# schematic.net
KiCad netlist of a schematic drawn in EAGLE
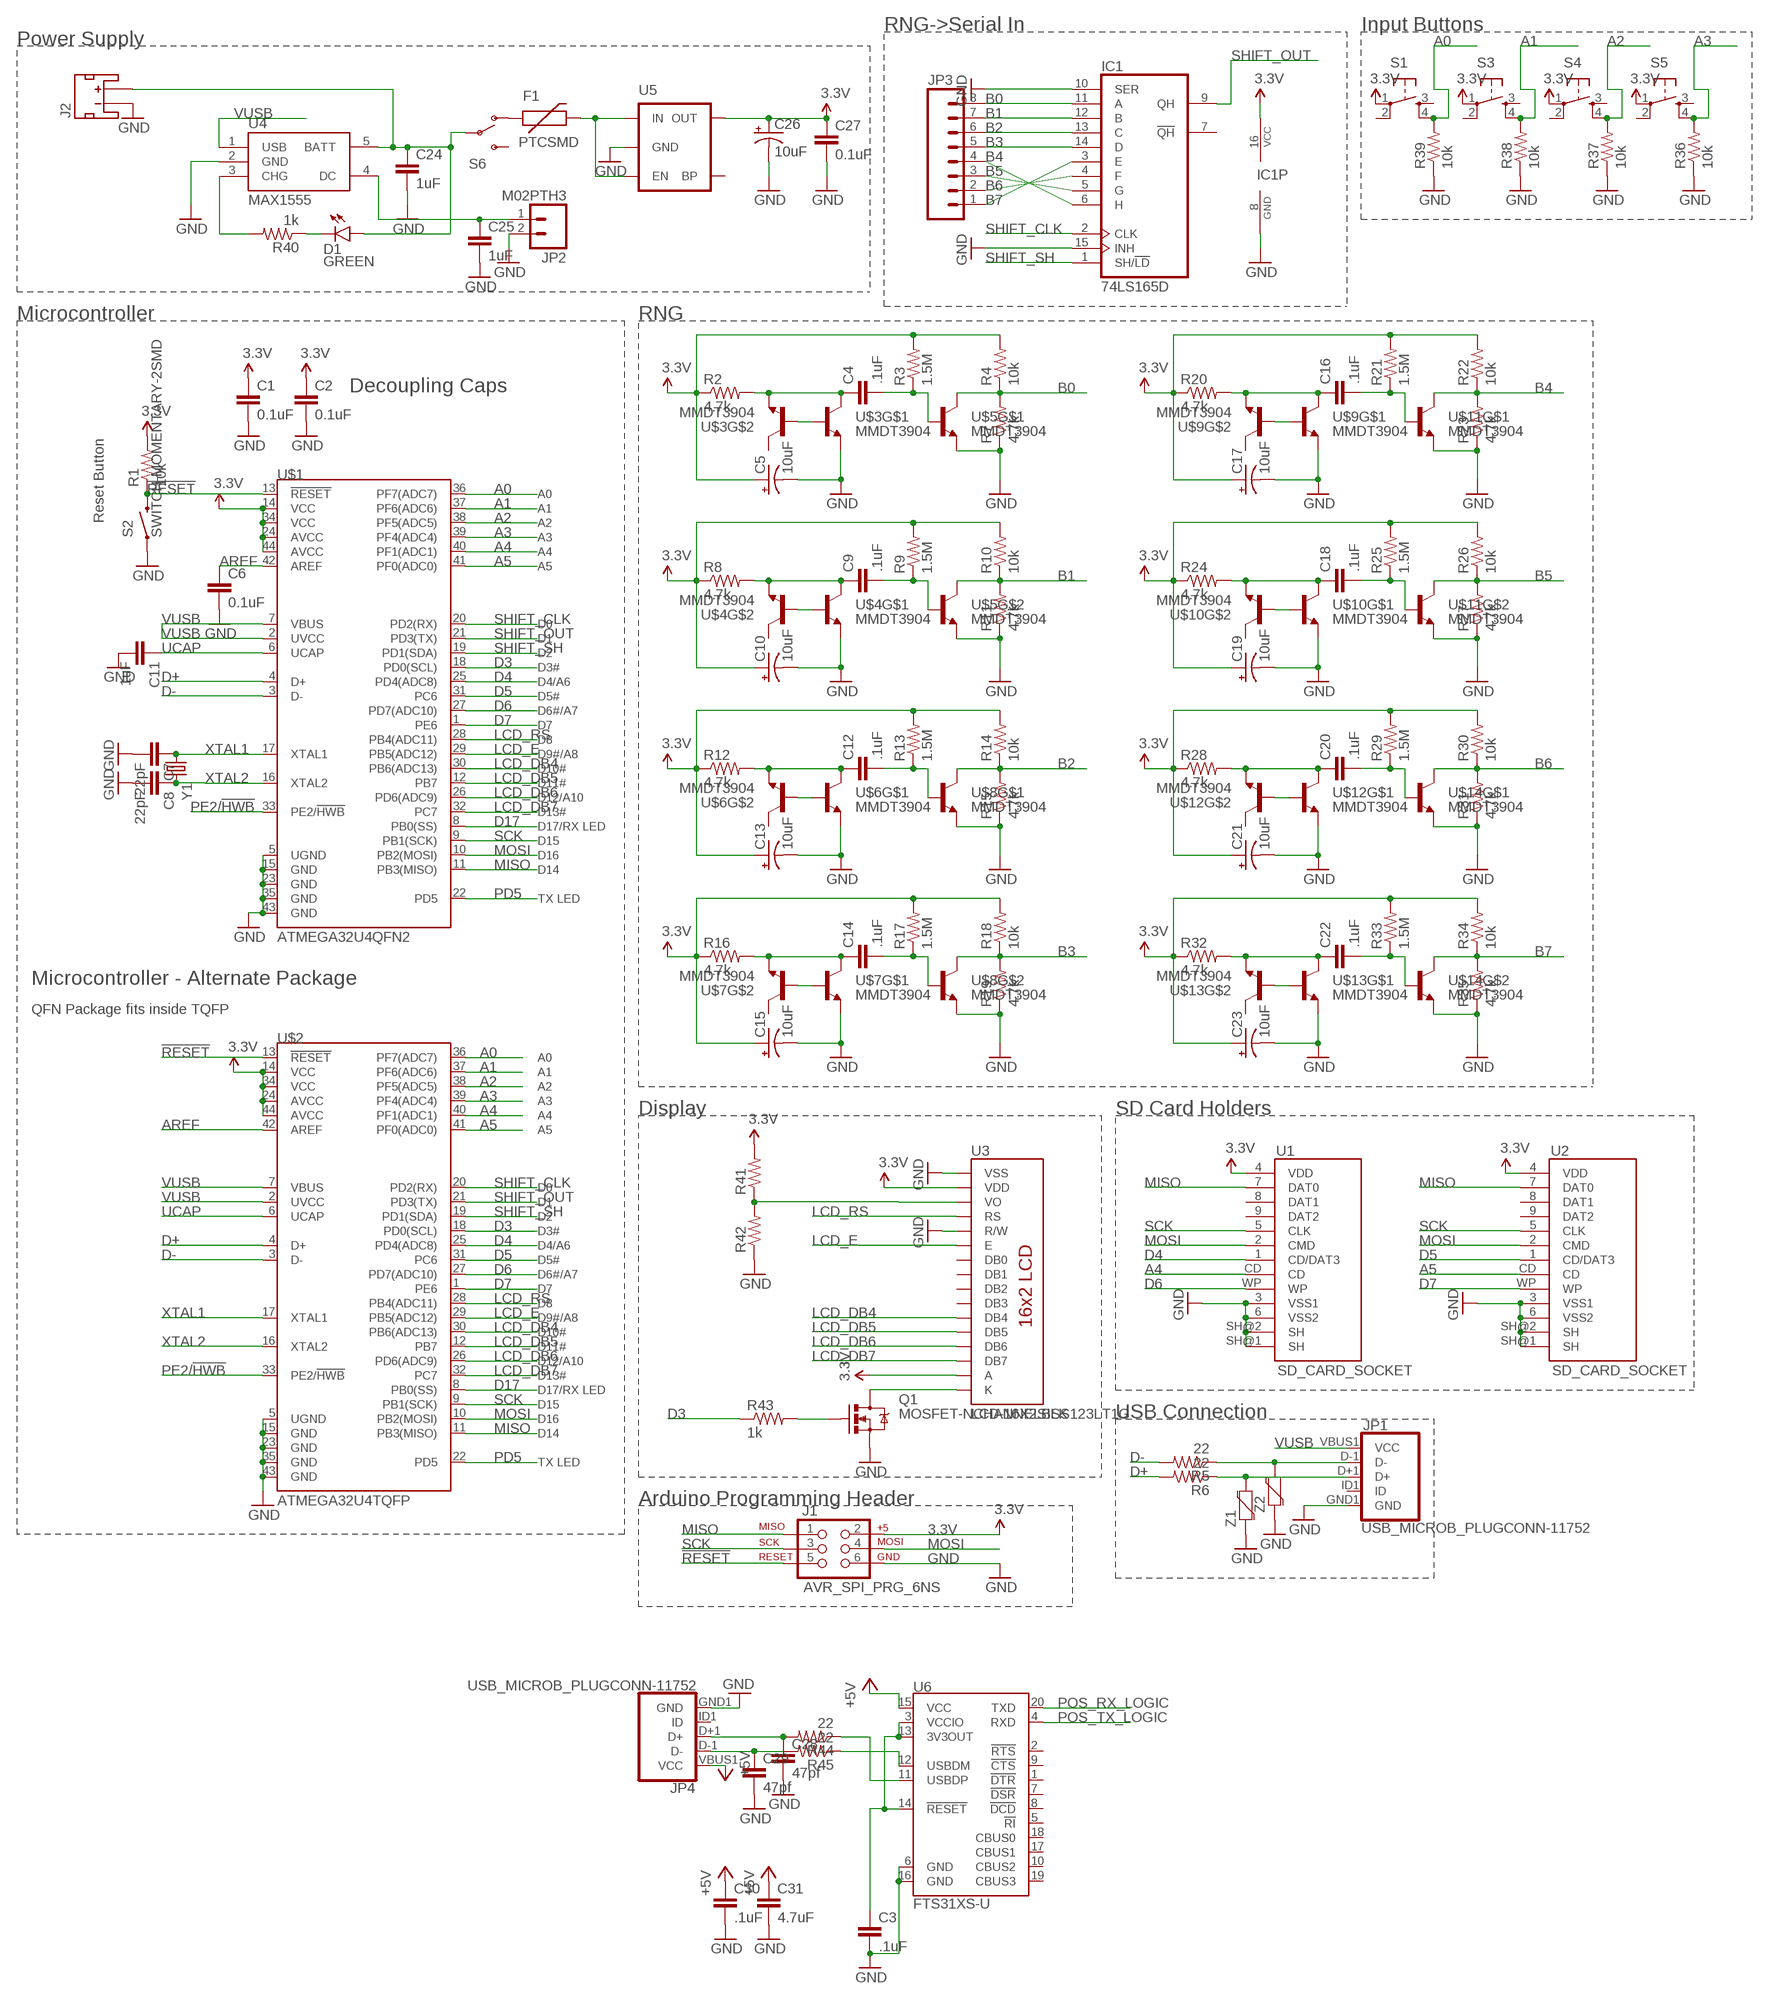
[diagram p0: schematic, sheet 1]

(export (version "E")
  (design (tool "Eeschema 10.0.6"))
  (components
    (comp (ref "C1")
      (value "0.1uF")
      (footprint "eagle-import:0603-CAP")
      (libsource (lib "eagle-import") (part "CAP0603-CAP"))
    )
    (comp (ref "C2")
      (value "0.1uF")
      (footprint "eagle-import:0603-CAP")
      (libsource (lib "eagle-import") (part "CAP0603-CAP"))
    )
    (comp (ref "C3")
      (value ".1uF")
      (footprint "eagle-import:0603-CAP")
      (libsource (lib "eagle-import") (part "CAP0603-CAP"))
    )
    (comp (ref "C4")
      (value ".1uF")
      (footprint "eagle-import:0603-CAP")
      (libsource (lib "eagle-import") (part "CAP0603-CAP"))
    )
    (comp (ref "C5")
      (value "10uF")
      (footprint "eagle-import:EIA3216")
      (libsource (lib "eagle-import") (part "CAP_POL1206"))
    )
    (comp (ref "C6")
      (value "0.1uF")
      (footprint "eagle-import:0603-CAP")
      (libsource (lib "eagle-import") (part "CAP0603-CAP"))
    )
    (comp (ref "C7")
      (value "22pF")
      (footprint "eagle-import:0603-CAP")
      (libsource (lib "eagle-import") (part "CAP0603-CAP"))
    )
    (comp (ref "C8")
      (value "22pF")
      (footprint "eagle-import:0603-CAP")
      (libsource (lib "eagle-import") (part "CAP0603-CAP"))
    )
    (comp (ref "C9")
      (value ".1uF")
      (footprint "eagle-import:0603-CAP")
      (libsource (lib "eagle-import") (part "CAP0603-CAP"))
    )
    (comp (ref "C10")
      (value "10uF")
      (footprint "eagle-import:EIA3216")
      (libsource (lib "eagle-import") (part "CAP_POL1206"))
    )
    (comp (ref "C11")
      (value "1uF")
      (footprint "eagle-import:0603-CAP")
      (libsource (lib "eagle-import") (part "CAP0603-CAP"))
    )
    (comp (ref "C12")
      (value ".1uF")
      (footprint "eagle-import:0603-CAP")
      (libsource (lib "eagle-import") (part "CAP0603-CAP"))
    )
    (comp (ref "C13")
      (value "10uF")
      (footprint "eagle-import:EIA3216")
      (libsource (lib "eagle-import") (part "CAP_POL1206"))
    )
    (comp (ref "C14")
      (value ".1uF")
      (footprint "eagle-import:0603-CAP")
      (libsource (lib "eagle-import") (part "CAP0603-CAP"))
    )
    (comp (ref "C15")
      (value "10uF")
      (footprint "eagle-import:EIA3216")
      (libsource (lib "eagle-import") (part "CAP_POL1206"))
    )
    (comp (ref "C16")
      (value ".1uF")
      (footprint "eagle-import:0603-CAP")
      (libsource (lib "eagle-import") (part "CAP0603-CAP"))
    )
    (comp (ref "C17")
      (value "10uF")
      (footprint "eagle-import:EIA3216")
      (libsource (lib "eagle-import") (part "CAP_POL1206"))
    )
    (comp (ref "C18")
      (value ".1uF")
      (footprint "eagle-import:0603-CAP")
      (libsource (lib "eagle-import") (part "CAP0603-CAP"))
    )
    (comp (ref "C19")
      (value "10uF")
      (footprint "eagle-import:EIA3216")
      (libsource (lib "eagle-import") (part "CAP_POL1206"))
    )
    (comp (ref "C20")
      (value ".1uF")
      (footprint "eagle-import:0603-CAP")
      (libsource (lib "eagle-import") (part "CAP0603-CAP"))
    )
    (comp (ref "C21")
      (value "10uF")
      (footprint "eagle-import:EIA3216")
      (libsource (lib "eagle-import") (part "CAP_POL1206"))
    )
    (comp (ref "C22")
      (value ".1uF")
      (footprint "eagle-import:0603-CAP")
      (libsource (lib "eagle-import") (part "CAP0603-CAP"))
    )
    (comp (ref "C23")
      (value "10uF")
      (footprint "eagle-import:EIA3216")
      (libsource (lib "eagle-import") (part "CAP_POL1206"))
    )
    (comp (ref "C24")
      (value "1uF")
      (footprint "eagle-import:0603-CAP")
      (libsource (lib "eagle-import") (part "CAP0603-CAP"))
    )
    (comp (ref "C25")
      (value "1uF")
      (footprint "eagle-import:0603-CAP")
      (libsource (lib "eagle-import") (part "CAP0603-CAP"))
    )
    (comp (ref "C26")
      (value "10uF")
      (footprint "eagle-import:EIA3216")
      (libsource (lib "eagle-import") (part "CAP_POL1206"))
    )
    (comp (ref "C27")
      (value "0.1uF")
      (footprint "eagle-import:0603-CAP")
      (libsource (lib "eagle-import") (part "CAP0603-CAP"))
    )
    (comp (ref "C28")
      (value "47pf")
      (footprint "eagle-import:0603-CAP")
      (libsource (lib "eagle-import") (part "CAP0603-CAP"))
    )
    (comp (ref "C29")
      (value "47pf")
      (footprint "eagle-import:0603-CAP")
      (libsource (lib "eagle-import") (part "CAP0603-CAP"))
    )
    (comp (ref "C30")
      (value ".1uF")
      (footprint "eagle-import:0603-CAP")
      (libsource (lib "eagle-import") (part "CAP0603-CAP"))
    )
    (comp (ref "C31")
      (value "4.7uF")
      (footprint "eagle-import:0603-CAP")
      (libsource (lib "eagle-import") (part "CAP0603-CAP"))
    )
    (comp (ref "D1")
      (value "GREEN")
      (footprint "eagle-import:LED-0603")
      (libsource (lib "eagle-import") (part "LED-GREEN0603"))
    )
    (comp (ref "F1")
      (value "PTCSMD")
      (footprint "eagle-import:PTC-1206")
      (libsource (lib "eagle-import") (part "PTCSMD"))
    )
    (comp (ref "IC1")
      (value "74LS165D")
      (footprint "eagle-import:SO16")
      (libsource (lib "eagle-import") (part "74165DLS"))
    )
    (comp (ref "J1")
      (value "AVR_SPI_PRG_6NS")
      (footprint "eagle-import:2X3-NS")
      (libsource (lib "eagle-import") (part "AVR_SPI_PRG_6NS"))
    )
    (comp (ref "J2")
      (value "JST_2MM_MALE")
      (footprint "eagle-import:JST-2-SMD")
      (libsource (lib "eagle-import") (part "JST_2MM_MALE"))
    )
    (comp (ref "JP1")
      (value "USB_MICROB_PLUGCONN-11752")
      (footprint "eagle-import:USB-B-MICRO-SMD_V03")
      (libsource (lib "eagle-import") (part "USB_MICROB_PLUGCONN-11752"))
    )
    (comp (ref "JP2")
      (value "M02PTH3")
      (footprint "eagle-import:1X02_LONGPADS")
      (libsource (lib "eagle-import") (part "M02PTH3"))
    )
    (comp (ref "JP3")
      (value "M081X08")
      (footprint "eagle-import:1X08")
      (libsource (lib "eagle-import") (part "M081X08"))
    )
    (comp (ref "JP4")
      (value "USB_MICROB_PLUGCONN-11752")
      (footprint "eagle-import:USB-B-MICRO-SMD_V03")
      (libsource (lib "eagle-import") (part "USB_MICROB_PLUGCONN-11752"))
    )
    (comp (ref "Q1")
      (value "MOSFET-NCHANNELBSS123LT1G")
      (footprint "eagle-import:SOT23")
      (libsource (lib "eagle-import") (part "MOSFET-NCHANNELBSS123LT1G"))
    )
    (comp (ref "R1")
      (value "10k")
      (footprint "eagle-import:0603-RES")
      (libsource (lib "eagle-import") (part "RESISTOR0603-RES"))
    )
    (comp (ref "R2")
      (value "4.7k")
      (footprint "eagle-import:0603-RES")
      (libsource (lib "eagle-import") (part "RESISTOR0603-RES"))
    )
    (comp (ref "R3")
      (value "1.5M")
      (footprint "eagle-import:0603-RES")
      (libsource (lib "eagle-import") (part "RESISTOR0603-RES"))
    )
    (comp (ref "R4")
      (value "10k")
      (footprint "eagle-import:0603-RES")
      (libsource (lib "eagle-import") (part "RESISTOR0603-RES"))
    )
    (comp (ref "R5")
      (value "22")
      (footprint "eagle-import:0603-RES")
      (libsource (lib "eagle-import") (part "RESISTOR0603-RES"))
    )
    (comp (ref "R6")
      (value "22")
      (footprint "eagle-import:0603-RES")
      (libsource (lib "eagle-import") (part "RESISTOR0603-RES"))
    )
    (comp (ref "R7")
      (value "4.7k")
      (footprint "eagle-import:0603-RES")
      (libsource (lib "eagle-import") (part "RESISTOR0603-RES"))
    )
    (comp (ref "R8")
      (value "4.7k")
      (footprint "eagle-import:0603-RES")
      (libsource (lib "eagle-import") (part "RESISTOR0603-RES"))
    )
    (comp (ref "R9")
      (value "1.5M")
      (footprint "eagle-import:0603-RES")
      (libsource (lib "eagle-import") (part "RESISTOR0603-RES"))
    )
    (comp (ref "R10")
      (value "10k")
      (footprint "eagle-import:0603-RES")
      (libsource (lib "eagle-import") (part "RESISTOR0603-RES"))
    )
    (comp (ref "R11")
      (value "4.7k")
      (footprint "eagle-import:0603-RES")
      (libsource (lib "eagle-import") (part "RESISTOR0603-RES"))
    )
    (comp (ref "R12")
      (value "4.7k")
      (footprint "eagle-import:0603-RES")
      (libsource (lib "eagle-import") (part "RESISTOR0603-RES"))
    )
    (comp (ref "R13")
      (value "1.5M")
      (footprint "eagle-import:0603-RES")
      (libsource (lib "eagle-import") (part "RESISTOR0603-RES"))
    )
    (comp (ref "R14")
      (value "10k")
      (footprint "eagle-import:0603-RES")
      (libsource (lib "eagle-import") (part "RESISTOR0603-RES"))
    )
    (comp (ref "R15")
      (value "4.7k")
      (footprint "eagle-import:0603-RES")
      (libsource (lib "eagle-import") (part "RESISTOR0603-RES"))
    )
    (comp (ref "R16")
      (value "4.7k")
      (footprint "eagle-import:0603-RES")
      (libsource (lib "eagle-import") (part "RESISTOR0603-RES"))
    )
    (comp (ref "R17")
      (value "1.5M")
      (footprint "eagle-import:0603-RES")
      (libsource (lib "eagle-import") (part "RESISTOR0603-RES"))
    )
    (comp (ref "R18")
      (value "10k")
      (footprint "eagle-import:0603-RES")
      (libsource (lib "eagle-import") (part "RESISTOR0603-RES"))
    )
    (comp (ref "R19")
      (value "4.7k")
      (footprint "eagle-import:0603-RES")
      (libsource (lib "eagle-import") (part "RESISTOR0603-RES"))
    )
    (comp (ref "R20")
      (value "4.7k")
      (footprint "eagle-import:0603-RES")
      (libsource (lib "eagle-import") (part "RESISTOR0603-RES"))
    )
    (comp (ref "R21")
      (value "1.5M")
      (footprint "eagle-import:0603-RES")
      (libsource (lib "eagle-import") (part "RESISTOR0603-RES"))
    )
    (comp (ref "R22")
      (value "10k")
      (footprint "eagle-import:0603-RES")
      (libsource (lib "eagle-import") (part "RESISTOR0603-RES"))
    )
    (comp (ref "R23")
      (value "4.7k")
      (footprint "eagle-import:0603-RES")
      (libsource (lib "eagle-import") (part "RESISTOR0603-RES"))
    )
    (comp (ref "R24")
      (value "4.7k")
      (footprint "eagle-import:0603-RES")
      (libsource (lib "eagle-import") (part "RESISTOR0603-RES"))
    )
    (comp (ref "R25")
      (value "1.5M")
      (footprint "eagle-import:0603-RES")
      (libsource (lib "eagle-import") (part "RESISTOR0603-RES"))
    )
    (comp (ref "R26")
      (value "10k")
      (footprint "eagle-import:0603-RES")
      (libsource (lib "eagle-import") (part "RESISTOR0603-RES"))
    )
    (comp (ref "R27")
      (value "4.7k")
      (footprint "eagle-import:0603-RES")
      (libsource (lib "eagle-import") (part "RESISTOR0603-RES"))
    )
    (comp (ref "R28")
      (value "4.7k")
      (footprint "eagle-import:0603-RES")
      (libsource (lib "eagle-import") (part "RESISTOR0603-RES"))
    )
    (comp (ref "R29")
      (value "1.5M")
      (footprint "eagle-import:0603-RES")
      (libsource (lib "eagle-import") (part "RESISTOR0603-RES"))
    )
    (comp (ref "R30")
      (value "10k")
      (footprint "eagle-import:0603-RES")
      (libsource (lib "eagle-import") (part "RESISTOR0603-RES"))
    )
    (comp (ref "R31")
      (value "4.7k")
      (footprint "eagle-import:0603-RES")
      (libsource (lib "eagle-import") (part "RESISTOR0603-RES"))
    )
    (comp (ref "R32")
      (value "4.7k")
      (footprint "eagle-import:0603-RES")
      (libsource (lib "eagle-import") (part "RESISTOR0603-RES"))
    )
    (comp (ref "R33")
      (value "1.5M")
      (footprint "eagle-import:0603-RES")
      (libsource (lib "eagle-import") (part "RESISTOR0603-RES"))
    )
    (comp (ref "R34")
      (value "10k")
      (footprint "eagle-import:0603-RES")
      (libsource (lib "eagle-import") (part "RESISTOR0603-RES"))
    )
    (comp (ref "R35")
      (value "4.7k")
      (footprint "eagle-import:0603-RES")
      (libsource (lib "eagle-import") (part "RESISTOR0603-RES"))
    )
    (comp (ref "R36")
      (value "10k")
      (footprint "eagle-import:0603-RES")
      (libsource (lib "eagle-import") (part "RESISTOR0603-RES"))
    )
    (comp (ref "R37")
      (value "10k")
      (footprint "eagle-import:0603-RES")
      (libsource (lib "eagle-import") (part "RESISTOR0603-RES"))
    )
    (comp (ref "R38")
      (value "10k")
      (footprint "eagle-import:0603-RES")
      (libsource (lib "eagle-import") (part "RESISTOR0603-RES"))
    )
    (comp (ref "R39")
      (value "10k")
      (footprint "eagle-import:0603-RES")
      (libsource (lib "eagle-import") (part "RESISTOR0603-RES"))
    )
    (comp (ref "R40")
      (value "1k")
      (footprint "eagle-import:0603-RES")
      (libsource (lib "eagle-import") (part "RESISTOR0603-RES"))
    )
    (comp (ref "R41")
      (value "RESISTOR0603-RES")
      (footprint "eagle-import:0603-RES")
      (libsource (lib "eagle-import") (part "RESISTOR0603-RES"))
    )
    (comp (ref "R42")
      (value "RESISTOR0603-RES")
      (footprint "eagle-import:0603-RES")
      (libsource (lib "eagle-import") (part "RESISTOR0603-RES"))
    )
    (comp (ref "R43")
      (value "1k")
      (footprint "eagle-import:0603-RES")
      (libsource (lib "eagle-import") (part "RESISTOR0603-RES"))
    )
    (comp (ref "R44")
      (value "22")
      (footprint "eagle-import:0603-RES")
      (libsource (lib "eagle-import") (part "RESISTOR0603-RES"))
    )
    (comp (ref "R45")
      (value "22")
      (footprint "eagle-import:0603-RES")
      (libsource (lib "eagle-import") (part "RESISTOR0603-RES"))
    )
    (comp (ref "S1")
      (value "TAC_SWITCHPTH")
      (footprint "eagle-import:TACTILE-PTH")
      (libsource (lib "eagle-import") (part "TAC_SWITCHPTH"))
    )
    (comp (ref "S2")
      (value "SWITCH-MOMENTARY-2SMD")
      (footprint "eagle-import:TACTILE-SWITCH-SMD")
      (libsource (lib "eagle-import") (part "SWITCH-MOMENTARY-2SMD"))
    )
    (comp (ref "S3")
      (value "TAC_SWITCHPTH")
      (footprint "eagle-import:TACTILE-PTH")
      (libsource (lib "eagle-import") (part "TAC_SWITCHPTH"))
    )
    (comp (ref "S4")
      (value "TAC_SWITCHPTH")
      (footprint "eagle-import:TACTILE-PTH")
      (libsource (lib "eagle-import") (part "TAC_SWITCHPTH"))
    )
    (comp (ref "S5")
      (value "TAC_SWITCHPTH")
      (footprint "eagle-import:TACTILE-PTH")
      (libsource (lib "eagle-import") (part "TAC_SWITCHPTH"))
    )
    (comp (ref "S6")
      (value "SWITCH-SPDTPTH")
      (footprint "eagle-import:SWITCH-SPDT")
      (libsource (lib "eagle-import") (part "SWITCH-SPDTPTH"))
    )
    (comp (ref "U$1")
      (value "ATMEGA32U4QFN2")
      (footprint "eagle-import:SPARKFUN-DIGITALIC_QFN-44-NOPAD")
      (libsource (lib "eagle-import") (part "ATMEGA32U4QFN2"))
    )
    (comp (ref "U$2")
      (value "ATMEGA32U4TQFP")
      (footprint "eagle-import:SPARKFUN-DIGITALIC_TQFP44")
      (libsource (lib "eagle-import") (part "ATMEGA32U4TQFP"))
    )
    (comp (ref "U$3")
      (value "MMDT3904")
      (footprint "eagle-import:SOT363")
      (libsource (lib "eagle-import") (part "TRANSISTOR_NPN2UPMMDT3904"))
    )
    (comp (ref "U$4")
      (value "MMDT3904")
      (footprint "eagle-import:SOT363")
      (libsource (lib "eagle-import") (part "TRANSISTOR_NPN2UPMMDT3904"))
    )
    (comp (ref "U$5")
      (value "MMDT3904")
      (footprint "eagle-import:SOT363")
      (libsource (lib "eagle-import") (part "TRANSISTOR_NPN2UPMMDT3904"))
    )
    (comp (ref "U$6")
      (value "MMDT3904")
      (footprint "eagle-import:SOT363")
      (libsource (lib "eagle-import") (part "TRANSISTOR_NPN2UPMMDT3904"))
    )
    (comp (ref "U$7")
      (value "MMDT3904")
      (footprint "eagle-import:SOT363")
      (libsource (lib "eagle-import") (part "TRANSISTOR_NPN2UPMMDT3904"))
    )
    (comp (ref "U$8")
      (value "MMDT3904")
      (footprint "eagle-import:SOT363")
      (libsource (lib "eagle-import") (part "TRANSISTOR_NPN2UPMMDT3904"))
    )
    (comp (ref "U$9")
      (value "MMDT3904")
      (footprint "eagle-import:SOT363")
      (libsource (lib "eagle-import") (part "TRANSISTOR_NPN2UPMMDT3904"))
    )
    (comp (ref "U$10")
      (value "MMDT3904")
      (footprint "eagle-import:SOT363")
      (libsource (lib "eagle-import") (part "TRANSISTOR_NPN2UPMMDT3904"))
    )
    (comp (ref "U$11")
      (value "MMDT3904")
      (footprint "eagle-import:SOT363")
      (libsource (lib "eagle-import") (part "TRANSISTOR_NPN2UPMMDT3904"))
    )
    (comp (ref "U$12")
      (value "MMDT3904")
      (footprint "eagle-import:SOT363")
      (libsource (lib "eagle-import") (part "TRANSISTOR_NPN2UPMMDT3904"))
    )
    (comp (ref "U$13")
      (value "MMDT3904")
      (footprint "eagle-import:SOT363")
      (libsource (lib "eagle-import") (part "TRANSISTOR_NPN2UPMMDT3904"))
    )
    (comp (ref "U$14")
      (value "MMDT3904")
      (footprint "eagle-import:SOT363")
      (libsource (lib "eagle-import") (part "TRANSISTOR_NPN2UPMMDT3904"))
    )
    (comp (ref "U1")
      (value "SD_CARD_SOCKET")
      (footprint "eagle-import:SD_1_1")
      (libsource (lib "eagle-import") (part "SD_CARD_SOCKET"))
    )
    (comp (ref "U2")
      (value "SD_CARD_SOCKET")
      (footprint "eagle-import:SD_1_1")
      (libsource (lib "eagle-import") (part "SD_CARD_SOCKET"))
    )
    (comp (ref "U3")
      (value "LCD-16X2SILK")
      (footprint "eagle-import:LCD-16X2")
      (libsource (lib "eagle-import") (part "LCD-16X2SILK"))
    )
    (comp (ref "U4")
      (value "MAX1555")
      (footprint "eagle-import:SOT23-5")
      (libsource (lib "eagle-import") (part "MAX1555"))
    )
    (comp (ref "U5")
      (value "MIC52053.3V")
      (footprint "eagle-import:SOT23-5")
      (libsource (lib "eagle-import") (part "MIC52053.3V"))
    )
    (comp (ref "U6")
      (value "FTS31XS-U")
      (footprint "eagle-import:SSOP20_L")
      (libsource (lib "eagle-import") (part "FT231XS"))
    )
    (comp (ref "Y1")
      (value "CRYSTALSMD")
      (footprint "eagle-import:HC49UP")
      (libsource (lib "eagle-import") (part "CRYSTALSMD"))
    )
    (comp (ref "Z1")
      (value "VARISTOR-0603")
      (footprint "eagle-import:0603-RES")
      (libsource (lib "eagle-import") (part "VARISTOR-0603"))
    )
    (comp (ref "Z2")
      (value "VARISTOR-0603")
      (footprint "eagle-import:0603-RES")
      (libsource (lib "eagle-import") (part "VARISTOR-0603"))
    )
  )
  (nets
    (net (code "1") (name "+5V") (class "Default")
      (node (ref "C30") (pin "1") (pinfunction "1_1") (pintype "passive"))
      (node (ref "C31") (pin "1") (pinfunction "1_1") (pintype "passive"))
      (node (ref "JP4") (pin "VBUS1") (pinfunction "VCC_VBUS1") (pintype "bidirectional"))
      (node (ref "U6") (pin "15") (pinfunction "VCC_15") (pintype "bidirectional"))
    )
    (net (code "2") (name "/A0") (class "Default")
      (node (ref "R39") (pin "2") (pinfunction "2_2") (pintype "passive"))
      (node (ref "S1") (pin "4") (pinfunction "4_4") (pintype "passive"))
      (node (ref "U$1") (pin "36") (pinfunction "PF7(ADC7)_36") (pintype "bidirectional"))
      (node (ref "U$2") (pin "36") (pinfunction "PF7(ADC7)_36") (pintype "bidirectional"))
    )
    (net (code "3") (name "/A1") (class "Default")
      (node (ref "R38") (pin "2") (pinfunction "2_2") (pintype "passive"))
      (node (ref "S3") (pin "4") (pinfunction "4_4") (pintype "passive"))
      (node (ref "U$1") (pin "37") (pinfunction "PF6(ADC6)_37") (pintype "bidirectional"))
      (node (ref "U$2") (pin "37") (pinfunction "PF6(ADC6)_37") (pintype "bidirectional"))
    )
    (net (code "4") (name "/A2") (class "Default")
      (node (ref "R37") (pin "2") (pinfunction "2_2") (pintype "passive"))
      (node (ref "S4") (pin "4") (pinfunction "4_4") (pintype "passive"))
      (node (ref "U$1") (pin "38") (pinfunction "PF5(ADC5)_38") (pintype "bidirectional"))
      (node (ref "U$2") (pin "38") (pinfunction "PF5(ADC5)_38") (pintype "bidirectional"))
    )
    (net (code "5") (name "/A3") (class "Default")
      (node (ref "R36") (pin "2") (pinfunction "2_2") (pintype "passive"))
      (node (ref "S5") (pin "4") (pinfunction "4_4") (pintype "passive"))
      (node (ref "U$1") (pin "39") (pinfunction "PF4(ADC4)_39") (pintype "bidirectional"))
      (node (ref "U$2") (pin "39") (pinfunction "PF4(ADC4)_39") (pintype "bidirectional"))
    )
    (net (code "6") (name "/A4") (class "Default")
      (node (ref "U$1") (pin "40") (pinfunction "PF1(ADC1)_40") (pintype "bidirectional"))
      (node (ref "U$2") (pin "40") (pinfunction "PF1(ADC1)_40") (pintype "bidirectional"))
      (node (ref "U1") (pin "CD") (pinfunction "CD_CD") (pintype "bidirectional"))
    )
    (net (code "7") (name "/A5") (class "Default")
      (node (ref "U$1") (pin "41") (pinfunction "PF0(ADC0)_41") (pintype "bidirectional"))
      (node (ref "U$2") (pin "41") (pinfunction "PF0(ADC0)_41") (pintype "bidirectional"))
      (node (ref "U2") (pin "CD") (pinfunction "CD_CD") (pintype "bidirectional"))
    )
    (net (code "8") (name "/AREF") (class "Default")
      (node (ref "C6") (pin "1") (pinfunction "1_1") (pintype "passive"))
      (node (ref "U$1") (pin "42") (pinfunction "AREF_42") (pintype "bidirectional"))
      (node (ref "U$2") (pin "42") (pinfunction "AREF_42") (pintype "bidirectional"))
    )
    (net (code "9") (name "/B0") (class "Default")
      (node (ref "IC1") (pin "11") (pinfunction "A_11") (pintype "input"))
      (node (ref "JP3") (pin "8") (pinfunction "8_8") (pintype "passive"))
      (node (ref "R4") (pin "1") (pinfunction "1_1") (pintype "passive"))
      (node (ref "R7") (pin "2") (pinfunction "2_2") (pintype "passive"))
      (node (ref "U$5") (pin "6") (pinfunction "C_6") (pintype "passive"))
    )
    (net (code "10") (name "/B1") (class "Default")
      (node (ref "IC1") (pin "12") (pinfunction "B_12") (pintype "input"))
      (node (ref "JP3") (pin "7") (pinfunction "7_7") (pintype "passive"))
      (node (ref "R10") (pin "1") (pinfunction "1_1") (pintype "passive"))
      (node (ref "R11") (pin "2") (pinfunction "2_2") (pintype "passive"))
      (node (ref "U$5") (pin "3") (pinfunction "C_3") (pintype "passive"))
    )
    (net (code "11") (name "/B2") (class "Default")
      (node (ref "IC1") (pin "13") (pinfunction "C_13") (pintype "input"))
      (node (ref "JP3") (pin "6") (pinfunction "6_6") (pintype "passive"))
      (node (ref "R14") (pin "1") (pinfunction "1_1") (pintype "passive"))
      (node (ref "R15") (pin "2") (pinfunction "2_2") (pintype "passive"))
      (node (ref "U$8") (pin "6") (pinfunction "C_6") (pintype "passive"))
    )
    (net (code "12") (name "/B3") (class "Default")
      (node (ref "IC1") (pin "14") (pinfunction "D_14") (pintype "input"))
      (node (ref "JP3") (pin "5") (pinfunction "5_5") (pintype "passive"))
      (node (ref "R18") (pin "1") (pinfunction "1_1") (pintype "passive"))
      (node (ref "R19") (pin "2") (pinfunction "2_2") (pintype "passive"))
      (node (ref "U$8") (pin "3") (pinfunction "C_3") (pintype "passive"))
    )
    (net (code "13") (name "/B4") (class "Default")
      (node (ref "IC1") (pin "3") (pinfunction "E_3") (pintype "input"))
      (node (ref "JP3") (pin "1") (pinfunction "1_1") (pintype "passive"))
      (node (ref "R22") (pin "1") (pinfunction "1_1") (pintype "passive"))
      (node (ref "R23") (pin "2") (pinfunction "2_2") (pintype "passive"))
      (node (ref "U$11") (pin "6") (pinfunction "C_6") (pintype "passive"))
    )
    (net (code "14") (name "/B5") (class "Default")
      (node (ref "IC1") (pin "4") (pinfunction "F_4") (pintype "input"))
      (node (ref "JP3") (pin "2") (pinfunction "2_2") (pintype "passive"))
      (node (ref "R26") (pin "1") (pinfunction "1_1") (pintype "passive"))
      (node (ref "R27") (pin "2") (pinfunction "2_2") (pintype "passive"))
      (node (ref "U$11") (pin "3") (pinfunction "C_3") (pintype "passive"))
    )
    (net (code "15") (name "/B6") (class "Default")
      (node (ref "IC1") (pin "5") (pinfunction "G_5") (pintype "input"))
      (node (ref "JP3") (pin "3") (pinfunction "3_3") (pintype "passive"))
      (node (ref "R30") (pin "1") (pinfunction "1_1") (pintype "passive"))
      (node (ref "R31") (pin "2") (pinfunction "2_2") (pintype "passive"))
      (node (ref "U$14") (pin "6") (pinfunction "C_6") (pintype "passive"))
    )
    (net (code "16") (name "/B7") (class "Default")
      (node (ref "IC1") (pin "6") (pinfunction "H_6") (pintype "input"))
      (node (ref "JP3") (pin "4") (pinfunction "4_4") (pintype "passive"))
      (node (ref "R34") (pin "1") (pinfunction "1_1") (pintype "passive"))
      (node (ref "R35") (pin "2") (pinfunction "2_2") (pintype "passive"))
      (node (ref "U$14") (pin "3") (pinfunction "C_3") (pintype "passive"))
    )
    (net (code "17") (name "/D+") (class "Default")
      (node (ref "R6") (pin "2") (pinfunction "2_2") (pintype "passive"))
      (node (ref "U$1") (pin "4") (pinfunction "D+_4") (pintype "bidirectional"))
      (node (ref "U$2") (pin "4") (pinfunction "D+_4") (pintype "bidirectional"))
    )
    (net (code "18") (name "/D-") (class "Default")
      (node (ref "R5") (pin "2") (pinfunction "2_2") (pintype "passive"))
      (node (ref "U$1") (pin "3") (pinfunction "D-_3") (pintype "bidirectional"))
      (node (ref "U$2") (pin "3") (pinfunction "D-_3") (pintype "bidirectional"))
    )
    (net (code "19") (name "/D3") (class "Default")
      (node (ref "R43") (pin "1") (pinfunction "1_1") (pintype "passive"))
      (node (ref "U$1") (pin "18") (pinfunction "PD0(SCL)_18") (pintype "bidirectional"))
      (node (ref "U$2") (pin "18") (pinfunction "PD0(SCL)_18") (pintype "bidirectional"))
    )
    (net (code "20") (name "/D4") (class "Default")
      (node (ref "U$1") (pin "25") (pinfunction "PD4(ADC8)_25") (pintype "bidirectional"))
      (node (ref "U$2") (pin "25") (pinfunction "PD4(ADC8)_25") (pintype "bidirectional"))
      (node (ref "U1") (pin "1") (pinfunction "CD/DAT3_1") (pintype "bidirectional"))
    )
    (net (code "21") (name "/D5") (class "Default")
      (node (ref "U$1") (pin "31") (pinfunction "PC6_31") (pintype "bidirectional"))
      (node (ref "U$2") (pin "31") (pinfunction "PC6_31") (pintype "bidirectional"))
      (node (ref "U2") (pin "1") (pinfunction "CD/DAT3_1") (pintype "bidirectional"))
    )
    (net (code "22") (name "/D6") (class "Default")
      (node (ref "U$1") (pin "27") (pinfunction "PD7(ADC10)_27") (pintype "bidirectional"))
      (node (ref "U$2") (pin "27") (pinfunction "PD7(ADC10)_27") (pintype "bidirectional"))
      (node (ref "U1") (pin "WP") (pinfunction "WP_WP") (pintype "bidirectional"))
    )
    (net (code "23") (name "/D7") (class "Default")
      (node (ref "U$1") (pin "1") (pinfunction "PE6_1") (pintype "bidirectional"))
      (node (ref "U$2") (pin "1") (pinfunction "PE6_1") (pintype "bidirectional"))
      (node (ref "U2") (pin "WP") (pinfunction "WP_WP") (pintype "bidirectional"))
    )
    (net (code "24") (name "/D17") (class "Default")
      (node (ref "U$1") (pin "8") (pinfunction "PB0(SS)_8") (pintype "bidirectional"))
      (node (ref "U$2") (pin "8") (pinfunction "PB0(SS)_8") (pintype "bidirectional"))
    )
    (net (code "25") (name "/LCD_DB4") (class "Default")
      (node (ref "U$1") (pin "30") (pinfunction "PB6(ADC13)_30") (pintype "bidirectional"))
      (node (ref "U$2") (pin "30") (pinfunction "PB6(ADC13)_30") (pintype "bidirectional"))
      (node (ref "U3") (pin "11") (pinfunction "DB4_11") (pintype "bidirectional"))
    )
    (net (code "26") (name "/LCD_DB5") (class "Default")
      (node (ref "U$1") (pin "12") (pinfunction "PB7_12") (pintype "bidirectional"))
      (node (ref "U$2") (pin "12") (pinfunction "PB7_12") (pintype "bidirectional"))
      (node (ref "U3") (pin "12") (pinfunction "DB5_12") (pintype "bidirectional"))
    )
    (net (code "27") (name "/LCD_DB6") (class "Default")
      (node (ref "U$1") (pin "26") (pinfunction "PD6(ADC9)_26") (pintype "bidirectional"))
      (node (ref "U$2") (pin "26") (pinfunction "PD6(ADC9)_26") (pintype "bidirectional"))
      (node (ref "U3") (pin "13") (pinfunction "DB6_13") (pintype "bidirectional"))
    )
    (net (code "28") (name "/LCD_DB7") (class "Default")
      (node (ref "U$1") (pin "32") (pinfunction "PC7_32") (pintype "bidirectional"))
      (node (ref "U$2") (pin "32") (pinfunction "PC7_32") (pintype "bidirectional"))
      (node (ref "U3") (pin "14") (pinfunction "DB7_14") (pintype "bidirectional"))
    )
    (net (code "29") (name "/LCD_E") (class "Default")
      (node (ref "U$1") (pin "29") (pinfunction "PB5(ADC12)_29") (pintype "bidirectional"))
      (node (ref "U$2") (pin "29") (pinfunction "PB5(ADC12)_29") (pintype "bidirectional"))
      (node (ref "U3") (pin "6") (pinfunction "E_6") (pintype "input"))
    )
    (net (code "30") (name "/LCD_RS") (class "Default")
      (node (ref "U$1") (pin "28") (pinfunction "PB4(ADC11)_28") (pintype "bidirectional"))
      (node (ref "U$2") (pin "28") (pinfunction "PB4(ADC11)_28") (pintype "bidirectional"))
      (node (ref "U3") (pin "4") (pinfunction "RS_4") (pintype "input"))
    )
    (net (code "31") (name "/MISO") (class "Default")
      (node (ref "J1") (pin "1") (pinfunction "1_1") (pintype "passive"))
      (node (ref "U$1") (pin "11") (pinfunction "PB3(MISO)_11") (pintype "bidirectional"))
      (node (ref "U$2") (pin "11") (pinfunction "PB3(MISO)_11") (pintype "bidirectional"))
      (node (ref "U1") (pin "7") (pinfunction "DAT0_7") (pintype "bidirectional"))
      (node (ref "U2") (pin "7") (pinfunction "DAT0_7") (pintype "bidirectional"))
    )
    (net (code "32") (name "/MOSI") (class "Default")
      (node (ref "J1") (pin "4") (pinfunction "4_4") (pintype "passive"))
      (node (ref "U$1") (pin "10") (pinfunction "PB2(MOSI)_10") (pintype "bidirectional"))
      (node (ref "U$2") (pin "10") (pinfunction "PB2(MOSI)_10") (pintype "bidirectional"))
      (node (ref "U1") (pin "2") (pinfunction "CMD_2") (pintype "bidirectional"))
      (node (ref "U2") (pin "2") (pinfunction "CMD_2") (pintype "bidirectional"))
    )
    (net (code "33") (name "/PD5") (class "Default")
      (node (ref "U$1") (pin "22") (pinfunction "PD5_22") (pintype "bidirectional"))
      (node (ref "U$2") (pin "22") (pinfunction "PD5_22") (pintype "bidirectional"))
    )
    (net (code "34") (name "/PE2{slash}~{HWB}") (class "Default")
      (node (ref "U$1") (pin "33") (pinfunction "PE2/~{HWB}_33") (pintype "bidirectional"))
      (node (ref "U$2") (pin "33") (pinfunction "PE2/~{HWB}_33") (pintype "bidirectional"))
    )
    (net (code "35") (name "/POS_RX_LOGIC") (class "Default")
      (node (ref "U6") (pin "20") (pinfunction "TXD_20") (pintype "bidirectional"))
    )
    (net (code "36") (name "/POS_TX_LOGIC") (class "Default")
      (node (ref "U6") (pin "4") (pinfunction "RXD_4") (pintype "bidirectional"))
    )
    (net (code "37") (name "/SCK") (class "Default")
      (node (ref "J1") (pin "3") (pinfunction "3_3") (pintype "passive"))
      (node (ref "U$1") (pin "9") (pinfunction "PB1(SCK)_9") (pintype "bidirectional"))
      (node (ref "U$2") (pin "9") (pinfunction "PB1(SCK)_9") (pintype "bidirectional"))
      (node (ref "U1") (pin "5") (pinfunction "CLK_5") (pintype "bidirectional"))
      (node (ref "U2") (pin "5") (pinfunction "CLK_5") (pintype "bidirectional"))
    )
    (net (code "38") (name "/SHIFT_CLK") (class "Default")
      (node (ref "IC1") (pin "2") (pinfunction "CLK_2") (pintype "input"))
      (node (ref "U$1") (pin "20") (pinfunction "PD2(RX)_20") (pintype "bidirectional"))
      (node (ref "U$2") (pin "20") (pinfunction "PD2(RX)_20") (pintype "bidirectional"))
    )
    (net (code "39") (name "/SHIFT_OUT") (class "Default")
      (node (ref "IC1") (pin "9") (pinfunction "QH_9") (pintype "output"))
      (node (ref "U$1") (pin "21") (pinfunction "PD3(TX)_21") (pintype "bidirectional"))
      (node (ref "U$2") (pin "21") (pinfunction "PD3(TX)_21") (pintype "bidirectional"))
    )
    (net (code "40") (name "/SHIFT_SH") (class "Default")
      (node (ref "IC1") (pin "1") (pinfunction "SH/~{LD}_1") (pintype "input"))
      (node (ref "U$1") (pin "19") (pinfunction "PD1(SDA)_19") (pintype "bidirectional"))
      (node (ref "U$2") (pin "19") (pinfunction "PD1(SDA)_19") (pintype "bidirectional"))
    )
    (net (code "41") (name "/UCAP") (class "Default")
      (node (ref "C11") (pin "1") (pinfunction "1_1") (pintype "passive"))
      (node (ref "U$1") (pin "6") (pinfunction "UCAP_6") (pintype "bidirectional"))
      (node (ref "U$2") (pin "6") (pinfunction "UCAP_6") (pintype "bidirectional"))
    )
    (net (code "42") (name "/VUSB") (class "Default")
      (node (ref "JP1") (pin "VBUS1") (pinfunction "VCC_VBUS1") (pintype "bidirectional"))
      (node (ref "U$1") (pin "2") (pinfunction "UVCC_2") (pintype "bidirectional"))
      (node (ref "U$1") (pin "7") (pinfunction "VBUS_7") (pintype "bidirectional"))
      (node (ref "U$2") (pin "2") (pinfunction "UVCC_2") (pintype "bidirectional"))
      (node (ref "U$2") (pin "7") (pinfunction "VBUS_7") (pintype "bidirectional"))
      (node (ref "U4") (pin "1") (pinfunction "USB_1") (pintype "bidirectional"))
    )
    (net (code "43") (name "/XTAL1") (class "Default")
      (node (ref "C7") (pin "1") (pinfunction "1_1") (pintype "passive"))
      (node (ref "U$1") (pin "17") (pinfunction "XTAL1_17") (pintype "bidirectional"))
      (node (ref "U$2") (pin "17") (pinfunction "XTAL1_17") (pintype "bidirectional"))
      (node (ref "Y1") (pin "1") (pinfunction "1_1") (pintype "passive"))
    )
    (net (code "44") (name "/XTAL2") (class "Default")
      (node (ref "C8") (pin "1") (pinfunction "1_1") (pintype "passive"))
      (node (ref "U$1") (pin "16") (pinfunction "XTAL2_16") (pintype "bidirectional"))
      (node (ref "U$2") (pin "16") (pinfunction "XTAL2_16") (pintype "bidirectional"))
      (node (ref "Y1") (pin "2") (pinfunction "2_2") (pintype "passive"))
    )
    (net (code "45") (name "/~{RESET}") (class "Default")
      (node (ref "J1") (pin "5") (pinfunction "5_5") (pintype "passive"))
      (node (ref "R1") (pin "1") (pinfunction "1_1") (pintype "passive"))
      (node (ref "S2") (pin "3") (pinfunction "2_3") (pintype "passive"))
      (node (ref "U$1") (pin "13") (pinfunction "~{RESET}_13") (pintype "bidirectional"))
      (node (ref "U$2") (pin "13") (pinfunction "~{RESET}_13") (pintype "bidirectional"))
    )
    (net (code "46") (name "3.3V") (class "Default")
      (node (ref "C1") (pin "1") (pinfunction "1_1") (pintype "passive"))
      (node (ref "C10") (pin "A") (pinfunction "+_A") (pintype "passive"))
      (node (ref "C13") (pin "A") (pinfunction "+_A") (pintype "passive"))
      (node (ref "C15") (pin "A") (pinfunction "+_A") (pintype "passive"))
      (node (ref "C17") (pin "A") (pinfunction "+_A") (pintype "passive"))
      (node (ref "C19") (pin "A") (pinfunction "+_A") (pintype "passive"))
      (node (ref "C2") (pin "1") (pinfunction "1_1") (pintype "passive"))
      (node (ref "C21") (pin "A") (pinfunction "+_A") (pintype "passive"))
      (node (ref "C23") (pin "A") (pinfunction "+_A") (pintype "passive"))
      (node (ref "C26") (pin "A") (pinfunction "+_A") (pintype "passive"))
      (node (ref "C27") (pin "1") (pinfunction "1_1") (pintype "passive"))
      (node (ref "C5") (pin "A") (pinfunction "+_A") (pintype "passive"))
      (node (ref "IC1") (pin "16") (pinfunction "VCC_16") (pintype "power_in"))
      (node (ref "J1") (pin "2") (pinfunction "2_2") (pintype "passive"))
      (node (ref "R1") (pin "2") (pinfunction "2_2") (pintype "passive"))
      (node (ref "R10") (pin "2") (pinfunction "2_2") (pintype "passive"))
      (node (ref "R12") (pin "1") (pinfunction "1_1") (pintype "passive"))
      (node (ref "R13") (pin "2") (pinfunction "2_2") (pintype "passive"))
      (node (ref "R14") (pin "2") (pinfunction "2_2") (pintype "passive"))
      (node (ref "R16") (pin "1") (pinfunction "1_1") (pintype "passive"))
      (node (ref "R17") (pin "2") (pinfunction "2_2") (pintype "passive"))
      (node (ref "R18") (pin "2") (pinfunction "2_2") (pintype "passive"))
      (node (ref "R2") (pin "1") (pinfunction "1_1") (pintype "passive"))
      (node (ref "R20") (pin "1") (pinfunction "1_1") (pintype "passive"))
      (node (ref "R21") (pin "2") (pinfunction "2_2") (pintype "passive"))
      (node (ref "R22") (pin "2") (pinfunction "2_2") (pintype "passive"))
      (node (ref "R24") (pin "1") (pinfunction "1_1") (pintype "passive"))
      (node (ref "R25") (pin "2") (pinfunction "2_2") (pintype "passive"))
      (node (ref "R26") (pin "2") (pinfunction "2_2") (pintype "passive"))
      (node (ref "R28") (pin "1") (pinfunction "1_1") (pintype "passive"))
      (node (ref "R29") (pin "2") (pinfunction "2_2") (pintype "passive"))
      (node (ref "R3") (pin "2") (pinfunction "2_2") (pintype "passive"))
      (node (ref "R30") (pin "2") (pinfunction "2_2") (pintype "passive"))
      (node (ref "R32") (pin "1") (pinfunction "1_1") (pintype "passive"))
      (node (ref "R33") (pin "2") (pinfunction "2_2") (pintype "passive"))
      (node (ref "R34") (pin "2") (pinfunction "2_2") (pintype "passive"))
      (node (ref "R4") (pin "2") (pinfunction "2_2") (pintype "passive"))
      (node (ref "R41") (pin "2") (pinfunction "2_2") (pintype "passive"))
      (node (ref "R8") (pin "1") (pinfunction "1_1") (pintype "passive"))
      (node (ref "R9") (pin "2") (pinfunction "2_2") (pintype "passive"))
      (node (ref "S1") (pin "1") (pinfunction "1_1") (pintype "passive"))
      (node (ref "S3") (pin "1") (pinfunction "1_1") (pintype "passive"))
      (node (ref "S4") (pin "1") (pinfunction "1_1") (pintype "passive"))
      (node (ref "S5") (pin "1") (pinfunction "1_1") (pintype "passive"))
      (node (ref "U$1") (pin "14") (pinfunction "VCC_14") (pintype "bidirectional"))
      (node (ref "U$1") (pin "24") (pinfunction "AVCC_24") (pintype "bidirectional"))
      (node (ref "U$1") (pin "34") (pinfunction "VCC_34") (pintype "bidirectional"))
      (node (ref "U$1") (pin "44") (pinfunction "AVCC_44") (pintype "bidirectional"))
      (node (ref "U$2") (pin "14") (pinfunction "VCC_14") (pintype "bidirectional"))
      (node (ref "U$2") (pin "24") (pinfunction "AVCC_24") (pintype "bidirectional"))
      (node (ref "U$2") (pin "34") (pinfunction "VCC_34") (pintype "bidirectional"))
      (node (ref "U$2") (pin "44") (pinfunction "AVCC_44") (pintype "bidirectional"))
      (node (ref "U1") (pin "4") (pinfunction "VDD_4") (pintype "power_in"))
      (node (ref "U2") (pin "4") (pinfunction "VDD_4") (pintype "power_in"))
      (node (ref "U3") (pin "15") (pinfunction "A_15") (pintype "power_in"))
      (node (ref "U3") (pin "2") (pinfunction "VDD_2") (pintype "power_in"))
      (node (ref "U5") (pin "5") (pinfunction "OUT_5") (pintype "passive"))
    )
    (net (code "47") (name "GND") (class "Default")
      (node (ref "C1") (pin "2") (pinfunction "2_2") (pintype "passive"))
      (node (ref "C10") (pin "C") (pinfunction "-_C") (pintype "passive"))
      (node (ref "C11") (pin "2") (pinfunction "2_2") (pintype "passive"))
      (node (ref "C13") (pin "C") (pinfunction "-_C") (pintype "passive"))
      (node (ref "C15") (pin "C") (pinfunction "-_C") (pintype "passive"))
      (node (ref "C17") (pin "C") (pinfunction "-_C") (pintype "passive"))
      (node (ref "C19") (pin "C") (pinfunction "-_C") (pintype "passive"))
      (node (ref "C2") (pin "2") (pinfunction "2_2") (pintype "passive"))
      (node (ref "C21") (pin "C") (pinfunction "-_C") (pintype "passive"))
      (node (ref "C23") (pin "C") (pinfunction "-_C") (pintype "passive"))
      (node (ref "C24") (pin "2") (pinfunction "2_2") (pintype "passive"))
      (node (ref "C25") (pin "2") (pinfunction "2_2") (pintype "passive"))
      (node (ref "C26") (pin "C") (pinfunction "-_C") (pintype "passive"))
      (node (ref "C27") (pin "2") (pinfunction "2_2") (pintype "passive"))
      (node (ref "C28") (pin "2") (pinfunction "2_2") (pintype "passive"))
      (node (ref "C29") (pin "2") (pinfunction "2_2") (pintype "passive"))
      (node (ref "C3") (pin "2") (pinfunction "2_2") (pintype "passive"))
      (node (ref "C30") (pin "2") (pinfunction "2_2") (pintype "passive"))
      (node (ref "C31") (pin "2") (pinfunction "2_2") (pintype "passive"))
      (node (ref "C5") (pin "C") (pinfunction "-_C") (pintype "passive"))
      (node (ref "C6") (pin "2") (pinfunction "2_2") (pintype "passive"))
      (node (ref "C7") (pin "2") (pinfunction "2_2") (pintype "passive"))
      (node (ref "C8") (pin "2") (pinfunction "2_2") (pintype "passive"))
      (node (ref "IC1") (pin "10") (pinfunction "SER_10") (pintype "input"))
      (node (ref "IC1") (pin "15") (pinfunction "INH_15") (pintype "input"))
      (node (ref "IC1") (pin "8") (pinfunction "GND_8") (pintype "power_in"))
      (node (ref "J1") (pin "6") (pinfunction "6_6") (pintype "passive"))
      (node (ref "J2") (pin "1") (pinfunction "-_1") (pintype "bidirectional"))
      (node (ref "JP1") (pin "GND1") (pinfunction "GND_GND1") (pintype "bidirectional"))
      (node (ref "JP2") (pin "2") (pinfunction "2_2") (pintype "passive"))
      (node (ref "JP4") (pin "GND1") (pinfunction "GND_GND1") (pintype "bidirectional"))
      (node (ref "Q1") (pin "2") (pinfunction "S_2") (pintype "passive"))
      (node (ref "R11") (pin "1") (pinfunction "1_1") (pintype "passive"))
      (node (ref "R15") (pin "1") (pinfunction "1_1") (pintype "passive"))
      (node (ref "R19") (pin "1") (pinfunction "1_1") (pintype "passive"))
      (node (ref "R23") (pin "1") (pinfunction "1_1") (pintype "passive"))
      (node (ref "R27") (pin "1") (pinfunction "1_1") (pintype "passive"))
      (node (ref "R31") (pin "1") (pinfunction "1_1") (pintype "passive"))
      (node (ref "R35") (pin "1") (pinfunction "1_1") (pintype "passive"))
      (node (ref "R36") (pin "1") (pinfunction "1_1") (pintype "passive"))
      (node (ref "R37") (pin "1") (pinfunction "1_1") (pintype "passive"))
      (node (ref "R38") (pin "1") (pinfunction "1_1") (pintype "passive"))
      (node (ref "R39") (pin "1") (pinfunction "1_1") (pintype "passive"))
      (node (ref "R42") (pin "1") (pinfunction "1_1") (pintype "passive"))
      (node (ref "R7") (pin "1") (pinfunction "1_1") (pintype "passive"))
      (node (ref "S2") (pin "1") (pinfunction "1_1") (pintype "passive"))
      (node (ref "U$1") (pin "15") (pinfunction "GND_15") (pintype "bidirectional"))
      (node (ref "U$1") (pin "23") (pinfunction "GND_23") (pintype "bidirectional"))
      (node (ref "U$1") (pin "35") (pinfunction "GND_35") (pintype "bidirectional"))
      (node (ref "U$1") (pin "43") (pinfunction "GND_43") (pintype "bidirectional"))
      (node (ref "U$1") (pin "5") (pinfunction "UGND_5") (pintype "bidirectional"))
      (node (ref "U$10") (pin "1") (pinfunction "E_1") (pintype "passive"))
      (node (ref "U$11") (pin "1") (pinfunction "E_1") (pintype "passive"))
      (node (ref "U$11") (pin "4") (pinfunction "E_4") (pintype "passive"))
      (node (ref "U$12") (pin "1") (pinfunction "E_1") (pintype "passive"))
      (node (ref "U$13") (pin "1") (pinfunction "E_1") (pintype "passive"))
      (node (ref "U$14") (pin "1") (pinfunction "E_1") (pintype "passive"))
      (node (ref "U$14") (pin "4") (pinfunction "E_4") (pintype "passive"))
      (node (ref "U$2") (pin "15") (pinfunction "GND_15") (pintype "bidirectional"))
      (node (ref "U$2") (pin "23") (pinfunction "GND_23") (pintype "bidirectional"))
      (node (ref "U$2") (pin "35") (pinfunction "GND_35") (pintype "bidirectional"))
      (node (ref "U$2") (pin "43") (pinfunction "GND_43") (pintype "bidirectional"))
      (node (ref "U$2") (pin "5") (pinfunction "UGND_5") (pintype "bidirectional"))
      (node (ref "U$3") (pin "1") (pinfunction "E_1") (pintype "passive"))
      (node (ref "U$4") (pin "1") (pinfunction "E_1") (pintype "passive"))
      (node (ref "U$5") (pin "1") (pinfunction "E_1") (pintype "passive"))
      (node (ref "U$5") (pin "4") (pinfunction "E_4") (pintype "passive"))
      (node (ref "U$6") (pin "1") (pinfunction "E_1") (pintype "passive"))
      (node (ref "U$7") (pin "1") (pinfunction "E_1") (pintype "passive"))
      (node (ref "U$8") (pin "1") (pinfunction "E_1") (pintype "passive"))
      (node (ref "U$8") (pin "4") (pinfunction "E_4") (pintype "passive"))
      (node (ref "U$9") (pin "1") (pinfunction "E_1") (pintype "passive"))
      (node (ref "U1") (pin "3") (pinfunction "VSS1_3") (pintype "power_in"))
      (node (ref "U1") (pin "6") (pinfunction "VSS2_6") (pintype "power_in"))
      (node (ref "U1") (pin "SH@1") (pinfunction "SH_SH@1") (pintype "bidirectional"))
      (node (ref "U1") (pin "SH@2") (pinfunction "SH_SH@2") (pintype "bidirectional"))
      (node (ref "U2") (pin "3") (pinfunction "VSS1_3") (pintype "power_in"))
      (node (ref "U2") (pin "6") (pinfunction "VSS2_6") (pintype "power_in"))
      (node (ref "U2") (pin "SH@1") (pinfunction "SH_SH@1") (pintype "bidirectional"))
      (node (ref "U2") (pin "SH@2") (pinfunction "SH_SH@2") (pintype "bidirectional"))
      (node (ref "U3") (pin "1") (pinfunction "VSS_1") (pintype "power_in"))
      (node (ref "U3") (pin "5") (pinfunction "R/W_5") (pintype "input"))
      (node (ref "U4") (pin "2") (pinfunction "GND_2") (pintype "bidirectional"))
      (node (ref "U5") (pin "2") (pinfunction "GND_2") (pintype "input"))
      (node (ref "U6") (pin "16") (pinfunction "GND_16") (pintype "bidirectional"))
      (node (ref "U6") (pin "6") (pinfunction "GND_6") (pintype "bidirectional"))
      (node (ref "Z1") (pin "1") (pinfunction "1_1") (pintype "passive"))
      (node (ref "Z2") (pin "1") (pinfunction "1_1") (pintype "passive"))
    )
    (net (code "48") (name "Net-(D1-PadC)") (class "Default")
      (node (ref "D1") (pin "C") (pinfunction "C_C") (pintype "passive"))
      (node (ref "R40") (pin "1") (pinfunction "1_1") (pintype "passive"))
    )
    (net (code "49") (name "Net-(J2-+)") (class "Default")
      (node (ref "C24") (pin "1") (pinfunction "1_1") (pintype "passive"))
      (node (ref "D1") (pin "A") (pinfunction "A_A") (pintype "passive"))
      (node (ref "J2") (pin "2") (pinfunction "+_2") (pintype "bidirectional"))
      (node (ref "S6") (pin "2") (pinfunction "P_2") (pintype "passive"))
      (node (ref "U4") (pin "5") (pinfunction "BATT_5") (pintype "bidirectional"))
    )
    (net (code "50") (name "Net-(JP1-D+)") (class "Default")
      (node (ref "JP1") (pin "D+1") (pinfunction "D+_D+1") (pintype "bidirectional"))
      (node (ref "R6") (pin "1") (pinfunction "1_1") (pintype "passive"))
      (node (ref "Z1") (pin "2") (pinfunction "2_2") (pintype "passive"))
    )
    (net (code "51") (name "Net-(JP1-D-)") (class "Default")
      (node (ref "JP1") (pin "D-1") (pinfunction "D-_D-1") (pintype "bidirectional"))
      (node (ref "R5") (pin "1") (pinfunction "1_1") (pintype "passive"))
      (node (ref "Z2") (pin "2") (pinfunction "2_2") (pintype "passive"))
    )
    (net (code "52") (name "Net-(JP4-D+)") (class "Default")
      (node (ref "C28") (pin "1") (pinfunction "1_1") (pintype "passive"))
      (node (ref "JP4") (pin "D+1") (pinfunction "D+_D+1") (pintype "bidirectional"))
      (node (ref "R44") (pin "2") (pinfunction "2_2") (pintype "passive"))
    )
    (net (code "53") (name "Net-(JP4-D-)") (class "Default")
      (node (ref "C29") (pin "1") (pinfunction "1_1") (pintype "passive"))
      (node (ref "JP4") (pin "D-1") (pinfunction "D-_D-1") (pintype "bidirectional"))
      (node (ref "R45") (pin "2") (pinfunction "2_2") (pintype "passive"))
    )
    (net (code "54") (name "Net-(Q1-D)") (class "Default")
      (node (ref "Q1") (pin "3") (pinfunction "D_3") (pintype "passive"))
      (node (ref "U3") (pin "16") (pinfunction "K_16") (pintype "power_in"))
    )
    (net (code "55") (name "Net-(Q1-G)") (class "Default")
      (node (ref "Q1") (pin "1") (pinfunction "G_1") (pintype "passive"))
      (node (ref "R43") (pin "2") (pinfunction "2_2") (pintype "passive"))
    )
    (net (code "56") (name "Net-(S6-O)") (class "Default")
      (node (ref "F1") (pin "1") (pinfunction "1_1") (pintype "bidirectional"))
      (node (ref "S6") (pin "1") (pinfunction "O_1") (pintype "passive"))
    )
    (net (code "57") (name "Net-(U$3A-B)") (class "Default")
      (node (ref "U$3") (pin "2") (pinfunction "B_2") (pintype "passive"))
      (node (ref "U$3") (pin "5") (pinfunction "B_5") (pintype "passive"))
    )
    (net (code "58") (name "Net-(U$3A-C)") (class "Default")
      (node (ref "C4") (pin "1") (pinfunction "1_1") (pintype "passive"))
      (node (ref "R2") (pin "2") (pinfunction "2_2") (pintype "passive"))
      (node (ref "U$3") (pin "4") (pinfunction "E_4") (pintype "passive"))
      (node (ref "U$3") (pin "6") (pinfunction "C_6") (pintype "passive"))
    )
    (net (code "59") (name "Net-(U$4A-B)") (class "Default")
      (node (ref "U$4") (pin "2") (pinfunction "B_2") (pintype "passive"))
      (node (ref "U$4") (pin "5") (pinfunction "B_5") (pintype "passive"))
    )
    (net (code "60") (name "Net-(U$4A-C)") (class "Default")
      (node (ref "C9") (pin "1") (pinfunction "1_1") (pintype "passive"))
      (node (ref "R8") (pin "2") (pinfunction "2_2") (pintype "passive"))
      (node (ref "U$4") (pin "4") (pinfunction "E_4") (pintype "passive"))
      (node (ref "U$4") (pin "6") (pinfunction "C_6") (pintype "passive"))
    )
    (net (code "61") (name "Net-(U$5A-B)") (class "Default")
      (node (ref "C4") (pin "2") (pinfunction "2_2") (pintype "passive"))
      (node (ref "R3") (pin "1") (pinfunction "1_1") (pintype "passive"))
      (node (ref "U$5") (pin "2") (pinfunction "B_2") (pintype "passive"))
    )
    (net (code "62") (name "Net-(U$5B-B)") (class "Default")
      (node (ref "C9") (pin "2") (pinfunction "2_2") (pintype "passive"))
      (node (ref "R9") (pin "1") (pinfunction "1_1") (pintype "passive"))
      (node (ref "U$5") (pin "5") (pinfunction "B_5") (pintype "passive"))
    )
    (net (code "63") (name "Net-(U$6A-B)") (class "Default")
      (node (ref "U$6") (pin "2") (pinfunction "B_2") (pintype "passive"))
      (node (ref "U$6") (pin "5") (pinfunction "B_5") (pintype "passive"))
    )
    (net (code "64") (name "Net-(U$6A-C)") (class "Default")
      (node (ref "C12") (pin "1") (pinfunction "1_1") (pintype "passive"))
      (node (ref "R12") (pin "2") (pinfunction "2_2") (pintype "passive"))
      (node (ref "U$6") (pin "4") (pinfunction "E_4") (pintype "passive"))
      (node (ref "U$6") (pin "6") (pinfunction "C_6") (pintype "passive"))
    )
    (net (code "65") (name "Net-(U$7A-B)") (class "Default")
      (node (ref "U$7") (pin "2") (pinfunction "B_2") (pintype "passive"))
      (node (ref "U$7") (pin "5") (pinfunction "B_5") (pintype "passive"))
    )
    (net (code "66") (name "Net-(U$7A-C)") (class "Default")
      (node (ref "C14") (pin "1") (pinfunction "1_1") (pintype "passive"))
      (node (ref "R16") (pin "2") (pinfunction "2_2") (pintype "passive"))
      (node (ref "U$7") (pin "4") (pinfunction "E_4") (pintype "passive"))
      (node (ref "U$7") (pin "6") (pinfunction "C_6") (pintype "passive"))
    )
    (net (code "67") (name "Net-(U$8A-B)") (class "Default")
      (node (ref "C12") (pin "2") (pinfunction "2_2") (pintype "passive"))
      (node (ref "R13") (pin "1") (pinfunction "1_1") (pintype "passive"))
      (node (ref "U$8") (pin "2") (pinfunction "B_2") (pintype "passive"))
    )
    (net (code "68") (name "Net-(U$8B-B)") (class "Default")
      (node (ref "C14") (pin "2") (pinfunction "2_2") (pintype "passive"))
      (node (ref "R17") (pin "1") (pinfunction "1_1") (pintype "passive"))
      (node (ref "U$8") (pin "5") (pinfunction "B_5") (pintype "passive"))
    )
    (net (code "69") (name "Net-(U$9A-B)") (class "Default")
      (node (ref "U$9") (pin "2") (pinfunction "B_2") (pintype "passive"))
      (node (ref "U$9") (pin "5") (pinfunction "B_5") (pintype "passive"))
    )
    (net (code "70") (name "Net-(U$9A-C)") (class "Default")
      (node (ref "C16") (pin "1") (pinfunction "1_1") (pintype "passive"))
      (node (ref "R20") (pin "2") (pinfunction "2_2") (pintype "passive"))
      (node (ref "U$9") (pin "4") (pinfunction "E_4") (pintype "passive"))
      (node (ref "U$9") (pin "6") (pinfunction "C_6") (pintype "passive"))
    )
    (net (code "71") (name "Net-(U$10A-B)") (class "Default")
      (node (ref "U$10") (pin "2") (pinfunction "B_2") (pintype "passive"))
      (node (ref "U$10") (pin "5") (pinfunction "B_5") (pintype "passive"))
    )
    (net (code "72") (name "Net-(U$10A-C)") (class "Default")
      (node (ref "C18") (pin "1") (pinfunction "1_1") (pintype "passive"))
      (node (ref "R24") (pin "2") (pinfunction "2_2") (pintype "passive"))
      (node (ref "U$10") (pin "4") (pinfunction "E_4") (pintype "passive"))
      (node (ref "U$10") (pin "6") (pinfunction "C_6") (pintype "passive"))
    )
    (net (code "73") (name "Net-(U$11A-B)") (class "Default")
      (node (ref "C16") (pin "2") (pinfunction "2_2") (pintype "passive"))
      (node (ref "R21") (pin "1") (pinfunction "1_1") (pintype "passive"))
      (node (ref "U$11") (pin "2") (pinfunction "B_2") (pintype "passive"))
    )
    (net (code "74") (name "Net-(U$11B-B)") (class "Default")
      (node (ref "C18") (pin "2") (pinfunction "2_2") (pintype "passive"))
      (node (ref "R25") (pin "1") (pinfunction "1_1") (pintype "passive"))
      (node (ref "U$11") (pin "5") (pinfunction "B_5") (pintype "passive"))
    )
    (net (code "75") (name "Net-(U$12A-B)") (class "Default")
      (node (ref "U$12") (pin "2") (pinfunction "B_2") (pintype "passive"))
      (node (ref "U$12") (pin "5") (pinfunction "B_5") (pintype "passive"))
    )
    (net (code "76") (name "Net-(U$12A-C)") (class "Default")
      (node (ref "C20") (pin "1") (pinfunction "1_1") (pintype "passive"))
      (node (ref "R28") (pin "2") (pinfunction "2_2") (pintype "passive"))
      (node (ref "U$12") (pin "4") (pinfunction "E_4") (pintype "passive"))
      (node (ref "U$12") (pin "6") (pinfunction "C_6") (pintype "passive"))
    )
    (net (code "77") (name "Net-(U$13A-B)") (class "Default")
      (node (ref "U$13") (pin "2") (pinfunction "B_2") (pintype "passive"))
      (node (ref "U$13") (pin "5") (pinfunction "B_5") (pintype "passive"))
    )
    (net (code "78") (name "Net-(U$13A-C)") (class "Default")
      (node (ref "C22") (pin "1") (pinfunction "1_1") (pintype "passive"))
      (node (ref "R32") (pin "2") (pinfunction "2_2") (pintype "passive"))
      (node (ref "U$13") (pin "4") (pinfunction "E_4") (pintype "passive"))
      (node (ref "U$13") (pin "6") (pinfunction "C_6") (pintype "passive"))
    )
    (net (code "79") (name "Net-(U$14A-B)") (class "Default")
      (node (ref "C20") (pin "2") (pinfunction "2_2") (pintype "passive"))
      (node (ref "R29") (pin "1") (pinfunction "1_1") (pintype "passive"))
      (node (ref "U$14") (pin "2") (pinfunction "B_2") (pintype "passive"))
    )
    (net (code "80") (name "Net-(U$14B-B)") (class "Default")
      (node (ref "C22") (pin "2") (pinfunction "2_2") (pintype "passive"))
      (node (ref "R33") (pin "1") (pinfunction "1_1") (pintype "passive"))
      (node (ref "U$14") (pin "5") (pinfunction "B_5") (pintype "passive"))
    )
    (net (code "81") (name "Net-(U3-VO)") (class "Default")
      (node (ref "R41") (pin "1") (pinfunction "1_1") (pintype "passive"))
      (node (ref "R42") (pin "2") (pinfunction "2_2") (pintype "passive"))
      (node (ref "U3") (pin "3") (pinfunction "VO_3") (pintype "bidirectional"))
    )
    (net (code "82") (name "Net-(U4-CHG)") (class "Default")
      (node (ref "R40") (pin "2") (pinfunction "2_2") (pintype "passive"))
      (node (ref "U4") (pin "3") (pinfunction "CHG_3") (pintype "bidirectional"))
    )
    (net (code "83") (name "Net-(U4-DC)") (class "Default")
      (node (ref "C25") (pin "1") (pinfunction "1_1") (pintype "passive"))
      (node (ref "JP2") (pin "1") (pinfunction "1_1") (pintype "passive"))
      (node (ref "U4") (pin "4") (pinfunction "DC_4") (pintype "bidirectional"))
    )
    (net (code "84") (name "Net-(U5-EN)") (class "Default")
      (node (ref "F1") (pin "2") (pinfunction "2_2") (pintype "bidirectional"))
      (node (ref "U5") (pin "1") (pinfunction "IN_1") (pintype "input"))
      (node (ref "U5") (pin "3") (pinfunction "EN_3") (pintype "input"))
    )
    (net (code "85") (name "Net-(U6-3V3OUT)") (class "Default")
      (node (ref "C3") (pin "1") (pinfunction "1_1") (pintype "passive"))
      (node (ref "U6") (pin "13") (pinfunction "3V3OUT_13") (pintype "bidirectional"))
      (node (ref "U6") (pin "14") (pinfunction "~{RESET}_14") (pintype "bidirectional"))
      (node (ref "U6") (pin "3") (pinfunction "VCCIO_3") (pintype "bidirectional"))
    )
    (net (code "86") (name "Net-(U6-USBDM)") (class "Default")
      (node (ref "R45") (pin "1") (pinfunction "1_1") (pintype "passive"))
      (node (ref "U6") (pin "12") (pinfunction "USBDM_12") (pintype "bidirectional"))
    )
    (net (code "87") (name "Net-(U6-USBDP)") (class "Default")
      (node (ref "R44") (pin "1") (pinfunction "1_1") (pintype "passive"))
      (node (ref "U6") (pin "11") (pinfunction "USBDP_11") (pintype "bidirectional"))
    )
    (net (code "88") (name "unconnected-(IC1A-~{QH}-Pad7)") (class "Default")
      (node (ref "IC1") (pin "7") (pinfunction "~{QH}_7") (pintype "output"))
    )
    (net (code "89") (name "unconnected-(J2-PAD1-PadNC1)") (class "Default")
      (node (ref "J2") (pin "NC1") (pinfunction "PAD1_NC1") (pintype "bidirectional"))
    )
    (net (code "90") (name "unconnected-(J2-PAD2-PadNC2)") (class "Default")
      (node (ref "J2") (pin "NC2") (pinfunction "PAD2_NC2") (pintype "bidirectional"))
    )
    (net (code "91") (name "unconnected-(JP1-ID-PadID1)") (class "Default")
      (node (ref "JP1") (pin "ID1") (pinfunction "ID_ID1") (pintype "bidirectional"))
    )
    (net (code "92") (name "unconnected-(JP4-ID-PadID1)") (class "Default")
      (node (ref "JP4") (pin "ID1") (pinfunction "ID_ID1") (pintype "bidirectional"))
    )
    (net (code "93") (name "unconnected-(S1-Pad2)") (class "Default")
      (node (ref "S1") (pin "2") (pinfunction "2_2") (pintype "passive"))
    )
    (net (code "94") (name "unconnected-(S1-Pad3)") (class "Default")
      (node (ref "S1") (pin "3") (pinfunction "3_3") (pintype "passive"))
    )
    (net (code "95") (name "unconnected-(S3-Pad2)") (class "Default")
      (node (ref "S3") (pin "2") (pinfunction "2_2") (pintype "passive"))
    )
    (net (code "96") (name "unconnected-(S3-Pad3)") (class "Default")
      (node (ref "S3") (pin "3") (pinfunction "3_3") (pintype "passive"))
    )
    (net (code "97") (name "unconnected-(S4-Pad2)") (class "Default")
      (node (ref "S4") (pin "2") (pinfunction "2_2") (pintype "passive"))
    )
    (net (code "98") (name "unconnected-(S4-Pad3)") (class "Default")
      (node (ref "S4") (pin "3") (pinfunction "3_3") (pintype "passive"))
    )
    (net (code "99") (name "unconnected-(S5-Pad2)") (class "Default")
      (node (ref "S5") (pin "2") (pinfunction "2_2") (pintype "passive"))
    )
    (net (code "100") (name "unconnected-(S5-Pad3)") (class "Default")
      (node (ref "S5") (pin "3") (pinfunction "3_3") (pintype "passive"))
    )
    (net (code "101") (name "unconnected-(S6-S-Pad3)") (class "Default")
      (node (ref "S6") (pin "3") (pinfunction "S_3") (pintype "passive"))
    )
    (net (code "102") (name "unconnected-(U$3B-C-Pad3)") (class "Default")
      (node (ref "U$3") (pin "3") (pinfunction "C_3") (pintype "passive"))
    )
    (net (code "103") (name "unconnected-(U$4B-C-Pad3)") (class "Default")
      (node (ref "U$4") (pin "3") (pinfunction "C_3") (pintype "passive"))
    )
    (net (code "104") (name "unconnected-(U$6B-C-Pad3)") (class "Default")
      (node (ref "U$6") (pin "3") (pinfunction "C_3") (pintype "passive"))
    )
    (net (code "105") (name "unconnected-(U$7B-C-Pad3)") (class "Default")
      (node (ref "U$7") (pin "3") (pinfunction "C_3") (pintype "passive"))
    )
    (net (code "106") (name "unconnected-(U$9B-C-Pad3)") (class "Default")
      (node (ref "U$9") (pin "3") (pinfunction "C_3") (pintype "passive"))
    )
    (net (code "107") (name "unconnected-(U$10B-C-Pad3)") (class "Default")
      (node (ref "U$10") (pin "3") (pinfunction "C_3") (pintype "passive"))
    )
    (net (code "108") (name "unconnected-(U$12B-C-Pad3)") (class "Default")
      (node (ref "U$12") (pin "3") (pinfunction "C_3") (pintype "passive"))
    )
    (net (code "109") (name "unconnected-(U$13B-C-Pad3)") (class "Default")
      (node (ref "U$13") (pin "3") (pinfunction "C_3") (pintype "passive"))
    )
    (net (code "110") (name "unconnected-(U1-DAT1-Pad8)") (class "Default")
      (node (ref "U1") (pin "8") (pinfunction "DAT1_8") (pintype "bidirectional"))
    )
    (net (code "111") (name "unconnected-(U1-DAT2-Pad9)") (class "Default")
      (node (ref "U1") (pin "9") (pinfunction "DAT2_9") (pintype "bidirectional"))
    )
    (net (code "112") (name "unconnected-(U2-DAT1-Pad8)") (class "Default")
      (node (ref "U2") (pin "8") (pinfunction "DAT1_8") (pintype "bidirectional"))
    )
    (net (code "113") (name "unconnected-(U2-DAT2-Pad9)") (class "Default")
      (node (ref "U2") (pin "9") (pinfunction "DAT2_9") (pintype "bidirectional"))
    )
    (net (code "114") (name "unconnected-(U3-DB0-Pad7)") (class "Default")
      (node (ref "U3") (pin "7") (pinfunction "DB0_7") (pintype "bidirectional"))
    )
    (net (code "115") (name "unconnected-(U3-DB1-Pad8)") (class "Default")
      (node (ref "U3") (pin "8") (pinfunction "DB1_8") (pintype "bidirectional"))
    )
    (net (code "116") (name "unconnected-(U3-DB2-Pad9)") (class "Default")
      (node (ref "U3") (pin "9") (pinfunction "DB2_9") (pintype "bidirectional"))
    )
    (net (code "117") (name "unconnected-(U3-DB3-Pad10)") (class "Default")
      (node (ref "U3") (pin "10") (pinfunction "DB3_10") (pintype "bidirectional"))
    )
    (net (code "118") (name "unconnected-(U5-BP-Pad4)") (class "Default")
      (node (ref "U5") (pin "4") (pinfunction "BP_4") (pintype "input"))
    )
    (net (code "119") (name "unconnected-(U6-CBUS0-Pad18)") (class "Default")
      (node (ref "U6") (pin "18") (pinfunction "CBUS0_18") (pintype "bidirectional"))
    )
    (net (code "120") (name "unconnected-(U6-CBUS1-Pad17)") (class "Default")
      (node (ref "U6") (pin "17") (pinfunction "CBUS1_17") (pintype "bidirectional"))
    )
    (net (code "121") (name "unconnected-(U6-CBUS2-Pad10)") (class "Default")
      (node (ref "U6") (pin "10") (pinfunction "CBUS2_10") (pintype "bidirectional"))
    )
    (net (code "122") (name "unconnected-(U6-CBUS3-Pad19)") (class "Default")
      (node (ref "U6") (pin "19") (pinfunction "CBUS3_19") (pintype "bidirectional"))
    )
    (net (code "123") (name "unconnected-(U6-~{CTS}-Pad9)") (class "Default")
      (node (ref "U6") (pin "9") (pinfunction "~{CTS}_9") (pintype "bidirectional"))
    )
    (net (code "124") (name "unconnected-(U6-~{DCD}-Pad8)") (class "Default")
      (node (ref "U6") (pin "8") (pinfunction "~{DCD}_8") (pintype "bidirectional"))
    )
    (net (code "125") (name "unconnected-(U6-~{DSR}-Pad7)") (class "Default")
      (node (ref "U6") (pin "7") (pinfunction "~{DSR}_7") (pintype "bidirectional"))
    )
    (net (code "126") (name "unconnected-(U6-~{DTR}-Pad1)") (class "Default")
      (node (ref "U6") (pin "1") (pinfunction "~{DTR}_1") (pintype "bidirectional"))
    )
    (net (code "127") (name "unconnected-(U6-~{RI}-Pad5)") (class "Default")
      (node (ref "U6") (pin "5") (pinfunction "~{RI}_5") (pintype "bidirectional"))
    )
    (net (code "128") (name "unconnected-(U6-~{RTS}-Pad2)") (class "Default")
      (node (ref "U6") (pin "2") (pinfunction "~{RTS}_2") (pintype "bidirectional"))
    )
  )
)
